# USBTinyISP_TH_Schematics.net
KiCad netlist of a schematic drawn in Altium Designer
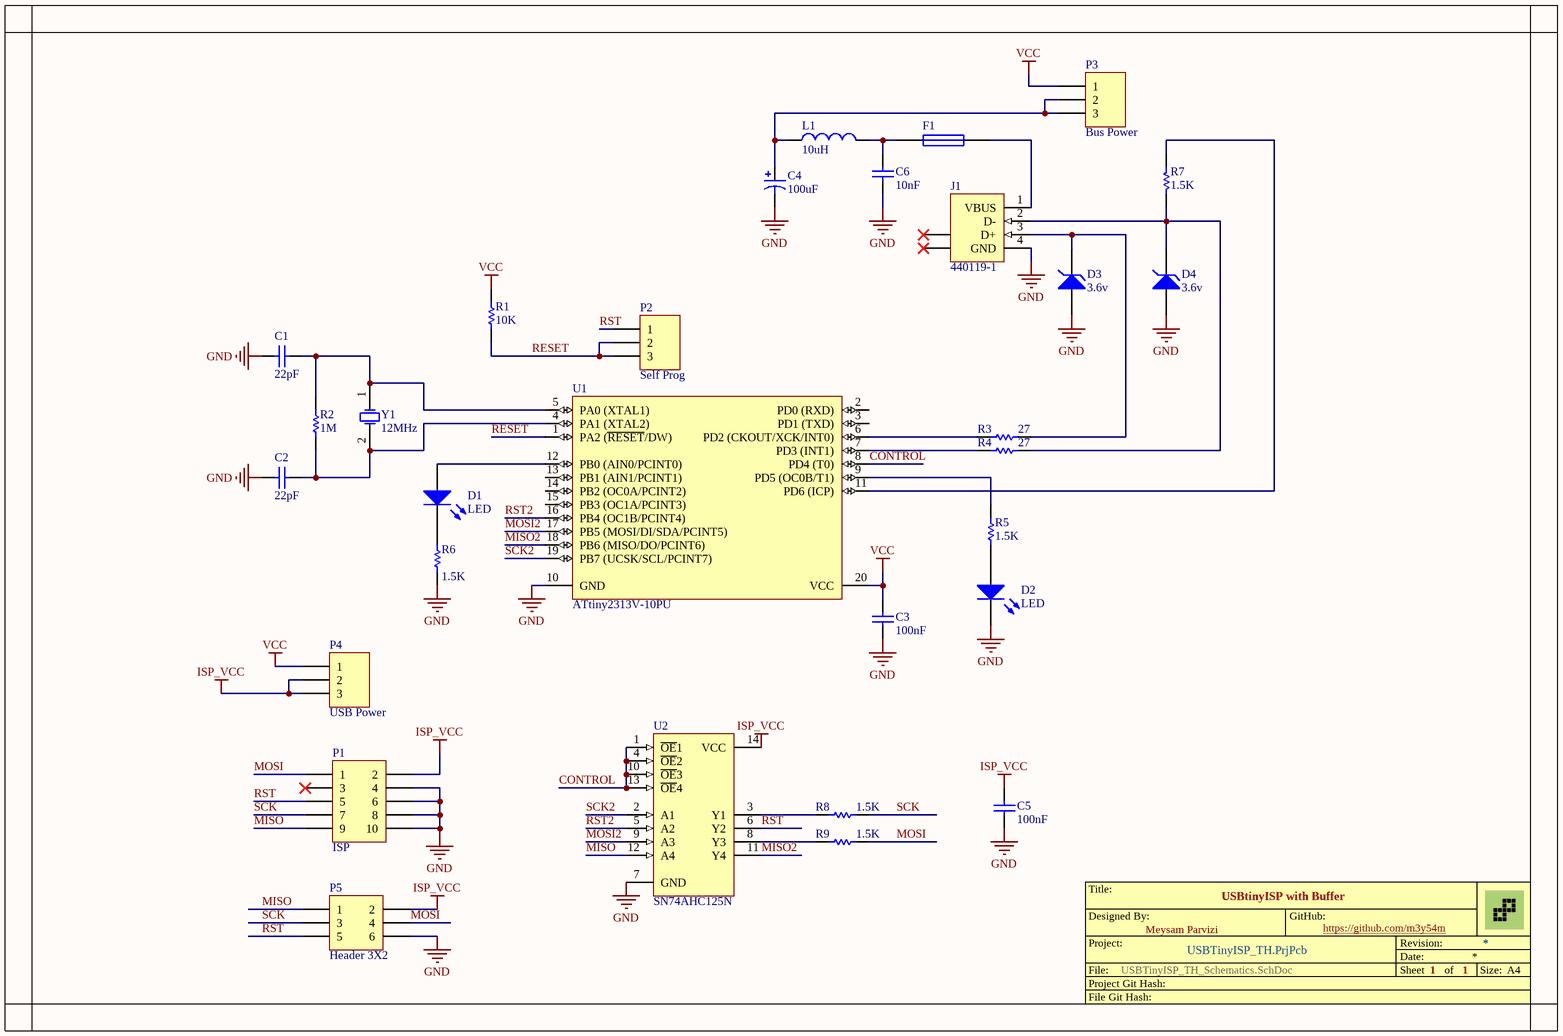
[diagram p0: USBTinyISP_TH_Schematics.SchDoc]

(export (version "E")
  (design (tool "Eeschema 10.0.6"))
  (components
    (comp (ref "C1")
      (value "22pF")
      (footprint "C1206")
      (description "Capacitor")
      (fields (field (name "Comment") "Cap") (field (name "PUBLISHER") "Altium Limited"))
      (libsource (lib "Miscellaneous Devices") (part "Cap"))
    )
    (comp (ref "C2")
      (value "22pF")
      (footprint "C1206")
      (description "Capacitor")
      (fields (field (name "Comment") "Cap") (field (name "PUBLISHER") "Altium Limited"))
      (libsource (lib "Miscellaneous Devices") (part "Cap"))
    )
    (comp (ref "C3")
      (value "100nF")
      (footprint "C1206")
      (description "Capacitor")
      (fields (field (name "Comment") "Cap") (field (name "PUBLISHER") "Altium Limited"))
      (libsource (lib "Miscellaneous Devices") (part "Cap"))
    )
    (comp (ref "C4")
      (value "100uF")
      (footprint "CAP-SMD1")
      (description "Polarized Capacitor (Radial)")
      (fields (field (name "Comment") "Cap Pol1") (field (name "PUBLISHER") "Altium Limited"))
      (libsource (lib "Miscellaneous Devices") (part "Cap Pol1"))
    )
    (comp (ref "C5")
      (value "100nF")
      (footprint "C1206")
      (description "Capacitor")
      (fields (field (name "Comment") "Cap") (field (name "PUBLISHER") "Altium Limited"))
      (libsource (lib "Miscellaneous Devices") (part "Cap"))
    )
    (comp (ref "C6")
      (value "10nF")
      (footprint "C1206")
      (description "Capacitor")
      (fields (field (name "Comment") "Cap") (field (name "PUBLISHER") "Altium Limited"))
      (libsource (lib "Miscellaneous Devices") (part "Cap"))
    )
    (comp (ref "D1")
      (value "LED")
      (footprint "3.5X2.8X1.9")
      (description "Typical RED GaAs LED")
      (fields (field (name "DESIGNER") "Meysam Parvizi") (field (name "EMAIL") "meysam.parvizi.ir@gmail.com"))
      (libsource (lib "mp") (part "LED"))
    )
    (comp (ref "D2")
      (value "LED")
      (footprint "3.5X2.8X1.9")
      (description "Typical RED GaAs LED")
      (fields (field (name "DESIGNER") "Meysam Parvizi") (field (name "EMAIL") "meysam.parvizi.ir@gmail.com"))
      (libsource (lib "mp") (part "LED"))
    )
    (comp (ref "D3")
      (value "3.6v")
      (footprint "DIODE-S")
      (description "Zener Diode")
      (fields (field (name "PUBLISHER") "Altium Limited"))
      (libsource (lib "Miscellaneous Devices") (part "D Zener"))
    )
    (comp (ref "D4")
      (value "3.6v")
      (footprint "DIODE-S")
      (description "Zener Diode")
      (fields (field (name "PUBLISHER") "Altium Limited"))
      (libsource (lib "Miscellaneous Devices") (part "D Zener"))
    )
    (comp (ref "F1")
      (value "Fuse 1")
      (footprint "C1206")
      (description "Fuse")
      (fields (field (name "PUBLISHER") "Altium Limited"))
      (libsource (lib "Miscellaneous Devices") (part "Fuse 1"))
    )
    (comp (ref "J1")
      (value "440119-1")
      (footprint "440119")
      (description "USB 1.1, Right Angle, Thru-Hole, B Type, Receptacle, 4 Position, Beige")
      (fields (field (name "PUBLISHER") "Altium Limited"))
      (libsource (lib "AMP Serial Bus USB") (part "440119-1"))
    )
    (comp (ref "L1")
      (value "10uH")
      (footprint "C1206")
      (description "Inductor")
      (fields (field (name "PUBLISHER") "Altium Limited"))
      (libsource (lib "Miscellaneous Devices") (part "Inductor"))
    )
    (comp (ref "P1")
      (value "ISP")
      (footprint "BOX2X5")
      (description "Box, 5-Pin, Dual row")
      (fields (field (name "DESIGNER") "Meysam Parvizi") (field (name "EMAIL") "meysam.parvizi.ir@gmail.com"))
      (libsource (lib "mp") (part "Box 5X2"))
    )
    (comp (ref "P2")
      (value "Self Prog")
      (footprint "HDR1X3")
      (description "Header, 3-Pin")
      (fields (field (name "PUBLISHER") "Altium Limited"))
      (libsource (lib "Miscellaneous Connectors") (part "Header 3"))
    )
    (comp (ref "P3")
      (value "Bus Power")
      (footprint "HDR1X3")
      (description "Header, 3-Pin")
      (fields (field (name "PUBLISHER") "Altium Limited"))
      (libsource (lib "Miscellaneous Connectors") (part "Header 3"))
    )
    (comp (ref "P4")
      (value "USB Power")
      (footprint "HDR1X3")
      (description "Header, 3-Pin")
      (fields (field (name "PUBLISHER") "Altium Limited"))
      (libsource (lib "Miscellaneous Connectors") (part "Header 3"))
    )
    (comp (ref "P5")
      (value "Header 3X2")
      (footprint "HDR2X3")
      (description "Header, 3-Pin, Dual row")
      (fields (field (name "PUBLISHER") "Altium Limited"))
      (libsource (lib "Miscellaneous Connectors") (part "Header 3X2"))
    )
    (comp (ref "R1")
      (value "10K")
      (footprint "C1206")
      (description "Resistor")
      (fields (field (name "Comment") "Res1") (field (name "PUBLISHER") "Altium Limited"))
      (libsource (lib "Miscellaneous Devices") (part "Res1"))
    )
    (comp (ref "R2")
      (value "1M")
      (footprint "C1206")
      (description "Resistor")
      (fields (field (name "Comment") "Res1") (field (name "PUBLISHER") "Altium Limited"))
      (libsource (lib "Miscellaneous Devices") (part "Res1"))
    )
    (comp (ref "R3")
      (value "27")
      (footprint "C1206")
      (description "Resistor")
      (fields (field (name "Comment") "Res1") (field (name "PUBLISHER") "Altium Limited"))
      (libsource (lib "Miscellaneous Devices") (part "Res1"))
    )
    (comp (ref "R4")
      (value "27")
      (footprint "C1206")
      (description "Resistor")
      (fields (field (name "Comment") "Res1") (field (name "PUBLISHER") "Altium Limited"))
      (libsource (lib "Miscellaneous Devices") (part "Res1"))
    )
    (comp (ref "R5")
      (value "1.5K")
      (footprint "C1206")
      (description "Resistor")
      (fields (field (name "Comment") "Res1") (field (name "PUBLISHER") "Altium Limited"))
      (libsource (lib "Miscellaneous Devices") (part "Res1"))
    )
    (comp (ref "R6")
      (value "1.5K")
      (footprint "C1206")
      (description "Resistor")
      (fields (field (name "Comment") "Res1") (field (name "PUBLISHER") "Altium Limited"))
      (libsource (lib "Miscellaneous Devices") (part "Res1"))
    )
    (comp (ref "R7")
      (value "1.5K")
      (footprint "C1206")
      (description "Resistor")
      (fields (field (name "Comment") "Res1") (field (name "PUBLISHER") "Altium Limited"))
      (libsource (lib "Miscellaneous Devices") (part "Res1"))
    )
    (comp (ref "R8")
      (value "1.5K")
      (footprint "C1206")
      (description "Resistor")
      (fields (field (name "Comment") "Res1") (field (name "PUBLISHER") "Altium Limited"))
      (libsource (lib "Miscellaneous Devices") (part "Res1"))
    )
    (comp (ref "R9")
      (value "1.5K")
      (footprint "C1206")
      (description "Resistor")
      (fields (field (name "Comment") "Res1") (field (name "PUBLISHER") "Altium Limited"))
      (libsource (lib "Miscellaneous Devices") (part "Res1"))
    )
    (comp (ref "U1")
      (value "ATtiny2313V-10PU")
      (footprint "DIP20")
      (fields (field (name "PUBLISHER") "Altium Limited"))
      (libsource (lib "Atmel Microcontroller 8-Bit tinyAVR") (part "ATtiny2313V-10PU"))
    )
    (comp (ref "U2")
      (value "SN74AHC125N")
      (footprint "DIP14")
      (description "Quadruple Bus Buffer Gate with 3-State Outputs")
      (fields (field (name "PUBLISHER") "Altium Limited"))
      (libsource (lib "TI Logic Buffer Line Driver") (part "SN74AHC125N"))
    )
    (comp (ref "Y1")
      (value "12MHz")
      (footprint "XTAL")
      (description "Crystal Oscillator")
      (fields
        (field (name "Comment") "XTAL")
        (field (name "DESIGNER") "Meysam Parvizi")
        (field (name "EMAIL") "meysam.parvizi.ir@gmail.com")
      )
      (libsource (lib "mp") (part "XTAL"))
    )
  )
  (nets
    (net (code "1") (name "/CONTROL") (class "Default")
      (node (ref "U1") (pin "8") (pinfunction "PD4_(T0)_8") (pintype "bidirectional"))
      (node (ref "U2") (pin "1") (pinfunction "~{OE}1_1") (pintype "input"))
      (node (ref "U2") (pin "10") (pinfunction "~{OE}3_10") (pintype "input"))
      (node (ref "U2") (pin "13") (pinfunction "~{OE}4_13") (pintype "input"))
      (node (ref "U2") (pin "4") (pinfunction "~{OE}2_4") (pintype "input"))
    )
    (net (code "2") (name "/MISO") (class "Default")
      (node (ref "P1") (pin "9") (pinfunction "9_9") (pintype "passive"))
      (node (ref "P5") (pin "1") (pinfunction "1_1") (pintype "passive"))
      (node (ref "U2") (pin "12") (pinfunction "A4_12") (pintype "input"))
    )
    (net (code "3") (name "/MISO2") (class "Default")
      (node (ref "U1") (pin "18") (pinfunction "PB6_(MISO/DO/PCINT6)_18") (pintype "bidirectional"))
      (node (ref "U2") (pin "11") (pinfunction "Y4_11") (pintype "tri_state"))
    )
    (net (code "4") (name "/MOSI") (class "Default")
      (node (ref "P1") (pin "1") (pinfunction "1_1") (pintype "passive"))
      (node (ref "P5") (pin "4") (pinfunction "4_4") (pintype "passive"))
      (node (ref "R9") (pin "2") (pinfunction "2_2") (pintype "passive"))
    )
    (net (code "5") (name "/MOSI2") (class "Default")
      (node (ref "U1") (pin "17") (pinfunction "PB5_(MOSI/DI/SDA/PCINT5)_17") (pintype "bidirectional"))
      (node (ref "U2") (pin "9") (pinfunction "A3_9") (pintype "input"))
    )
    (net (code "6") (name "/RESET") (class "Default")
      (node (ref "P2") (pin "2") (pinfunction "2_2") (pintype "passive"))
      (node (ref "P2") (pin "3") (pinfunction "3_3") (pintype "passive"))
      (node (ref "R1") (pin "1") (pinfunction "1_1") (pintype "passive"))
      (node (ref "U1") (pin "1") (pinfunction "PA2_(~{RESET}/DW)_1") (pintype "bidirectional"))
    )
    (net (code "7") (name "/RST") (class "Default")
      (node (ref "P1") (pin "5") (pinfunction "5_5") (pintype "passive"))
      (node (ref "P2") (pin "1") (pinfunction "1_1") (pintype "passive"))
      (node (ref "P5") (pin "5") (pinfunction "5_5") (pintype "passive"))
      (node (ref "U2") (pin "6") (pinfunction "Y2_6") (pintype "tri_state"))
    )
    (net (code "8") (name "/RST2") (class "Default")
      (node (ref "U1") (pin "16") (pinfunction "PB4_(OC1B/PCINT4)_16") (pintype "bidirectional"))
      (node (ref "U2") (pin "5") (pinfunction "A2_5") (pintype "input"))
    )
    (net (code "9") (name "/SCK") (class "Default")
      (node (ref "P1") (pin "7") (pinfunction "7_7") (pintype "passive"))
      (node (ref "P5") (pin "3") (pinfunction "3_3") (pintype "passive"))
      (node (ref "R8") (pin "2") (pinfunction "2_2") (pintype "passive"))
    )
    (net (code "10") (name "/SCK2") (class "Default")
      (node (ref "U1") (pin "19") (pinfunction "PB7_(UCSK/SCL/PCINT7)_19") (pintype "bidirectional"))
      (node (ref "U2") (pin "2") (pinfunction "A1_2") (pintype "input"))
    )
    (net (code "11") (name "GND") (class "Default")
      (node (ref "C1") (pin "1") (pinfunction "1_1") (pintype "passive"))
      (node (ref "C2") (pin "1") (pinfunction "1_1") (pintype "passive"))
      (node (ref "C3") (pin "1") (pinfunction "1_1") (pintype "passive"))
      (node (ref "C4") (pin "2") (pinfunction "2_2") (pintype "passive"))
      (node (ref "C5") (pin "1") (pinfunction "1_1") (pintype "passive"))
      (node (ref "C6") (pin "1") (pinfunction "1_1") (pintype "passive"))
      (node (ref "D2") (pin "2") (pinfunction "K_2") (pintype "passive"))
      (node (ref "D3") (pin "1") (pinfunction "A_1") (pintype "passive"))
      (node (ref "D4") (pin "1") (pinfunction "A_1") (pintype "passive"))
      (node (ref "J1") (pin "4") (pinfunction "GND_4") (pintype "power_in"))
      (node (ref "P1") (pin "10") (pinfunction "10_10") (pintype "passive"))
      (node (ref "P1") (pin "4") (pinfunction "4_4") (pintype "passive"))
      (node (ref "P1") (pin "6") (pinfunction "6_6") (pintype "passive"))
      (node (ref "P1") (pin "8") (pinfunction "8_8") (pintype "passive"))
      (node (ref "P5") (pin "6") (pinfunction "6_6") (pintype "passive"))
      (node (ref "R6") (pin "2") (pinfunction "2_2") (pintype "passive"))
      (node (ref "U1") (pin "10") (pinfunction "GND_10") (pintype "power_in"))
      (node (ref "U2") (pin "7") (pinfunction "GND_7") (pintype "power_in"))
    )
    (net (code "12") (name "ISP_VCC") (class "Default")
      (node (ref "C5") (pin "2") (pinfunction "2_2") (pintype "passive"))
      (node (ref "P1") (pin "2") (pinfunction "2_2") (pintype "passive"))
      (node (ref "P4") (pin "2") (pinfunction "2_2") (pintype "passive"))
      (node (ref "P4") (pin "3") (pinfunction "3_3") (pintype "passive"))
      (node (ref "P5") (pin "2") (pinfunction "2_2") (pintype "passive"))
      (node (ref "U2") (pin "14") (pinfunction "VCC_14") (pintype "power_in"))
    )
    (net (code "13") (name "Net-(C4-Pad1)") (class "Default")
      (node (ref "C4") (pin "1") (pinfunction "1_1") (pintype "passive"))
      (node (ref "L1") (pin "1") (pinfunction "1_1") (pintype "passive"))
      (node (ref "P3") (pin "2") (pinfunction "2_2") (pintype "passive"))
      (node (ref "P3") (pin "3") (pinfunction "3_3") (pintype "passive"))
    )
    (net (code "14") (name "Net-(C6-Pad2)") (class "Default")
      (node (ref "C6") (pin "2") (pinfunction "2_2") (pintype "passive"))
      (node (ref "F1") (pin "1") (pinfunction "1_1") (pintype "passive"))
      (node (ref "L1") (pin "2") (pinfunction "2_2") (pintype "passive"))
    )
    (net (code "15") (name "Net-(D1-A)") (class "Default")
      (node (ref "D1") (pin "1") (pinfunction "A_1") (pintype "passive"))
      (node (ref "U1") (pin "12") (pinfunction "PB0_(AIN0/PCINT0)_12") (pintype "bidirectional"))
    )
    (net (code "16") (name "Net-(D1-K)") (class "Default")
      (node (ref "D1") (pin "2") (pinfunction "K_2") (pintype "passive"))
      (node (ref "R6") (pin "1") (pinfunction "1_1") (pintype "passive"))
    )
    (net (code "17") (name "Net-(D2-A)") (class "Default")
      (node (ref "D2") (pin "1") (pinfunction "A_1") (pintype "passive"))
      (node (ref "R5") (pin "2") (pinfunction "2_2") (pintype "passive"))
    )
    (net (code "18") (name "Net-(D3-K)") (class "Default")
      (node (ref "D3") (pin "2") (pinfunction "K_2") (pintype "passive"))
      (node (ref "J1") (pin "3") (pinfunction "D+_3") (pintype "input"))
      (node (ref "R3") (pin "1") (pinfunction "1_1") (pintype "passive"))
    )
    (net (code "19") (name "Net-(D4-K)") (class "Default")
      (node (ref "D4") (pin "2") (pinfunction "K_2") (pintype "passive"))
      (node (ref "J1") (pin "2") (pinfunction "D-_2") (pintype "input"))
      (node (ref "R4") (pin "1") (pinfunction "1_1") (pintype "passive"))
      (node (ref "R7") (pin "1") (pinfunction "1_1") (pintype "passive"))
    )
    (net (code "20") (name "Net-(J1-VBUS)") (class "Default")
      (node (ref "F1") (pin "2") (pinfunction "2_2") (pintype "passive"))
      (node (ref "J1") (pin "1") (pinfunction "VBUS_1") (pintype "power_in"))
    )
    (net (code "21") (name "Net-(U1-PA0_(XTAL1))") (class "Default")
      (node (ref "C1") (pin "2") (pinfunction "2_2") (pintype "passive"))
      (node (ref "R2") (pin "2") (pinfunction "2_2") (pintype "passive"))
      (node (ref "U1") (pin "5") (pinfunction "PA0_(XTAL1)_5") (pintype "bidirectional"))
      (node (ref "Y1") (pin "1") (pinfunction "OSC1_1") (pintype "passive"))
    )
    (net (code "22") (name "Net-(U1-PA1_(XTAL2))") (class "Default")
      (node (ref "C2") (pin "2") (pinfunction "2_2") (pintype "passive"))
      (node (ref "R2") (pin "1") (pinfunction "1_1") (pintype "passive"))
      (node (ref "U1") (pin "4") (pinfunction "PA1_(XTAL2)_4") (pintype "bidirectional"))
      (node (ref "Y1") (pin "2") (pinfunction "OSC2_2") (pintype "passive"))
    )
    (net (code "23") (name "Net-(U1-PD2_(CKOUT{slash}XCK{slash}INT0))") (class "Default")
      (node (ref "R3") (pin "2") (pinfunction "2_2") (pintype "passive"))
      (node (ref "U1") (pin "6") (pinfunction "PD2_(CKOUT/XCK/INT0)_6") (pintype "bidirectional"))
    )
    (net (code "24") (name "Net-(U1-PD3_(INT1))") (class "Default")
      (node (ref "R4") (pin "2") (pinfunction "2_2") (pintype "passive"))
      (node (ref "U1") (pin "7") (pinfunction "PD3_(INT1)_7") (pintype "bidirectional"))
    )
    (net (code "25") (name "Net-(U1-PD5_(OC0B{slash}T1))") (class "Default")
      (node (ref "R5") (pin "1") (pinfunction "1_1") (pintype "passive"))
      (node (ref "U1") (pin "9") (pinfunction "PD5_(OC0B/T1)_9") (pintype "bidirectional"))
    )
    (net (code "26") (name "Net-(U1-PD6_(ICP))") (class "Default")
      (node (ref "R7") (pin "2") (pinfunction "2_2") (pintype "passive"))
      (node (ref "U1") (pin "11") (pinfunction "PD6_(ICP)_11") (pintype "bidirectional"))
    )
    (net (code "27") (name "Net-(U2-Y1)") (class "Default")
      (node (ref "R8") (pin "1") (pinfunction "1_1") (pintype "passive"))
      (node (ref "U2") (pin "3") (pinfunction "Y1_3") (pintype "tri_state"))
    )
    (net (code "28") (name "Net-(U2-Y3)") (class "Default")
      (node (ref "R9") (pin "1") (pinfunction "1_1") (pintype "passive"))
      (node (ref "U2") (pin "8") (pinfunction "Y3_8") (pintype "tri_state"))
    )
    (net (code "29") (name "VCC") (class "Default")
      (node (ref "C3") (pin "2") (pinfunction "2_2") (pintype "passive"))
      (node (ref "P3") (pin "1") (pinfunction "1_1") (pintype "passive"))
      (node (ref "P4") (pin "1") (pinfunction "1_1") (pintype "passive"))
      (node (ref "R1") (pin "2") (pinfunction "2_2") (pintype "passive"))
      (node (ref "U1") (pin "20") (pinfunction "VCC_20") (pintype "power_in"))
    )
    (net (code "30") (name "unconnected-(J1-SHLD-Pad5)") (class "Default")
      (node (ref "J1") (pin "5") (pinfunction "SHLD_5") (pintype "passive+no_connect"))
    )
    (net (code "31") (name "unconnected-(J1-SHLD-Pad6)") (class "Default")
      (node (ref "J1") (pin "6") (pinfunction "SHLD_6") (pintype "passive+no_connect"))
    )
    (net (code "32") (name "unconnected-(P1-Pad3)") (class "Default")
      (node (ref "P1") (pin "3") (pinfunction "3_3") (pintype "passive+no_connect"))
    )
    (net (code "33") (name "unconnected-(U1-PB1_(AIN1{slash}PCINT1)-Pad13)") (class "Default")
      (node (ref "U1") (pin "13") (pinfunction "PB1_(AIN1/PCINT1)_13") (pintype "bidirectional"))
    )
    (net (code "34") (name "unconnected-(U1-PB2_(OC0A{slash}PCINT2)-Pad14)") (class "Default")
      (node (ref "U1") (pin "14") (pinfunction "PB2_(OC0A/PCINT2)_14") (pintype "bidirectional"))
    )
    (net (code "35") (name "unconnected-(U1-PB3_(OC1A{slash}PCINT3)-Pad15)") (class "Default")
      (node (ref "U1") (pin "15") (pinfunction "PB3_(OC1A/PCINT3)_15") (pintype "bidirectional"))
    )
    (net (code "36") (name "unconnected-(U1-PD0_(RXD)-Pad2)") (class "Default")
      (node (ref "U1") (pin "2") (pinfunction "PD0_(RXD)_2") (pintype "bidirectional"))
    )
    (net (code "37") (name "unconnected-(U1-PD1_(TXD)-Pad3)") (class "Default")
      (node (ref "U1") (pin "3") (pinfunction "PD1_(TXD)_3") (pintype "bidirectional"))
    )
  )
)
